# MdA_CPU.net
KiCad netlist of a schematic drawn in Altium Designer
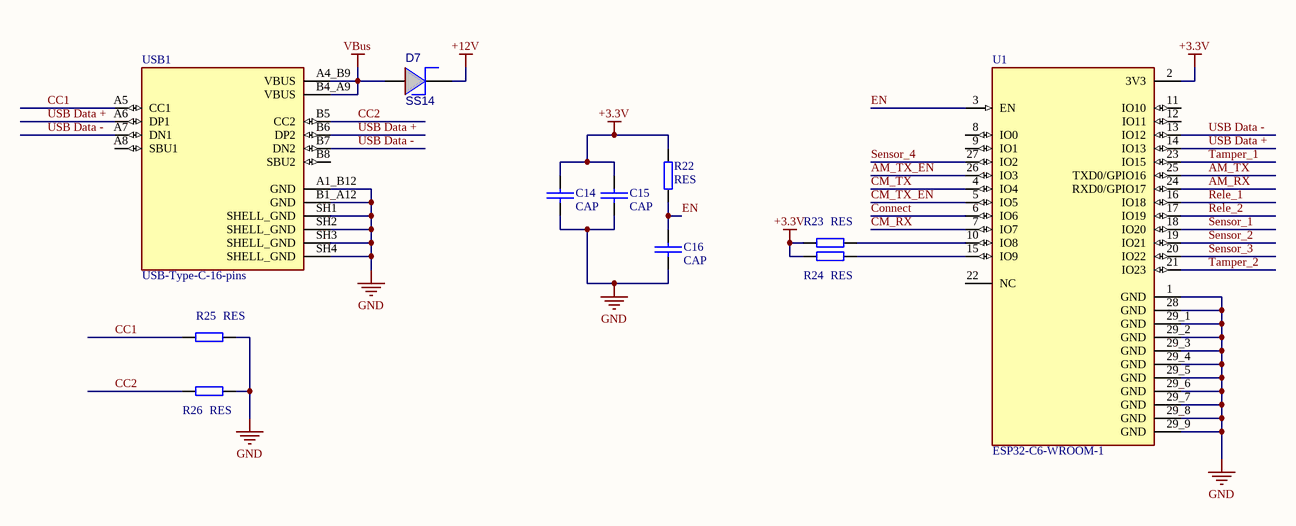
[diagram p0: MdA_CPU.SchDoc]

(export (version "E")
  (design (tool "Eeschema 10.0.6"))
  (components
    (comp (ref "C14") (value "CAP") (footprint "C_0402") (libsource (lib "Modulo de apertura") (part "CAP")))
    (comp (ref "C15") (value "CAP") (footprint "C_0402") (libsource (lib "Modulo de apertura") (part "CAP")))
    (comp (ref "C16") (value "CAP") (footprint "C_0402") (libsource (lib "Modulo de apertura") (part "CAP")))
    (comp (ref "D7")
      (value "SS14")
      (footprint "IDCI_WifiNode:D_SMA")
      (description "Diode Shottky")
      (libsource (lib "WifiNode") (part "DIODO_SH"))
    )
    (comp (ref "R22") (value "RES") (footprint "R_0402") (libsource (lib "Modulo de apertura") (part "RES")))
    (comp (ref "R23") (value "RES") (footprint "R_0402") (libsource (lib "Modulo de apertura") (part "RES")))
    (comp (ref "R24") (value "RES") (footprint "R_0402") (libsource (lib "Modulo de apertura") (part "RES")))
    (comp (ref "R25") (value "RES") (footprint "R_0402") (libsource (lib "Modulo de apertura") (part "RES")))
    (comp (ref "R26") (value "RES") (footprint "R_0402") (libsource (lib "Modulo de apertura") (part "RES")))
    (comp (ref "U1")
      (value "ESP32-C6-WROOM-1")
      (footprint "ESP32-C6-WROOM-1")
      (libsource (lib "Modulo de apertura") (part "ESP32-C6-WROOM-1"))
    )
    (comp (ref "USB1")
      (value "USB-Type-C-16-pins")
      (footprint "GCT_USB4105GFA120")
      (libsource (lib "Modulo de apertura") (part "USB-Type-C-16-pins"))
    )
  )
  (nets
    (net (code "1") (name "+3.3V") (class "Default")
      (node (ref "C14") (pin "1") (pinfunction "1_1") (pintype "passive"))
      (node (ref "C15") (pin "1") (pinfunction "1_1") (pintype "passive"))
      (node (ref "R22") (pin "1") (pinfunction "1_1") (pintype "passive"))
      (node (ref "R23") (pin "2") (pinfunction "2_2") (pintype "passive"))
      (node (ref "R24") (pin "2") (pinfunction "2_2") (pintype "passive"))
      (node (ref "U1") (pin "2") (pinfunction "3V3_2") (pintype "power_in"))
    )
    (net (code "2") (name "+12V") (class "Default")
      (node (ref "D7") (pin "2") (pinfunction "K_2") (pintype "passive"))
    )
    (net (code "3") (name "/AM_RX") (class "Default")
      (node (ref "U1") (pin "24") (pinfunction "RXD0/GPIO17_24") (pintype "bidirectional"))
    )
    (net (code "4") (name "/AM_TX") (class "Default")
      (node (ref "U1") (pin "25") (pinfunction "TXD0/GPIO16_25") (pintype "bidirectional"))
    )
    (net (code "5") (name "/AM_TX_EN") (class "Default")
      (node (ref "U1") (pin "26") (pinfunction "IO3_26") (pintype "bidirectional"))
    )
    (net (code "6") (name "/CC1") (class "Default")
      (node (ref "R25") (pin "2") (pinfunction "2_2") (pintype "passive"))
      (node (ref "USB1") (pin "A5") (pinfunction "CC1_A5") (pintype "bidirectional"))
    )
    (net (code "7") (name "/CC2") (class "Default")
      (node (ref "R26") (pin "2") (pinfunction "2_2") (pintype "passive"))
      (node (ref "USB1") (pin "B5") (pinfunction "CC2_B5") (pintype "bidirectional"))
    )
    (net (code "8") (name "/CM_RX") (class "Default")
      (node (ref "U1") (pin "7") (pinfunction "IO7_7") (pintype "bidirectional"))
    )
    (net (code "9") (name "/CM_TX") (class "Default")
      (node (ref "U1") (pin "4") (pinfunction "IO4_4") (pintype "bidirectional"))
    )
    (net (code "10") (name "/CM_TX_EN") (class "Default")
      (node (ref "U1") (pin "5") (pinfunction "IO5_5") (pintype "bidirectional"))
    )
    (net (code "11") (name "/Connect") (class "Default")
      (node (ref "U1") (pin "6") (pinfunction "IO6_6") (pintype "bidirectional"))
    )
    (net (code "12") (name "/EN") (class "Default")
      (node (ref "C16") (pin "1") (pinfunction "1_1") (pintype "passive"))
      (node (ref "R22") (pin "2") (pinfunction "2_2") (pintype "passive"))
      (node (ref "U1") (pin "3") (pinfunction "EN_3") (pintype "input"))
    )
    (net (code "13") (name "/Rele_1") (class "Default")
      (node (ref "U1") (pin "16") (pinfunction "IO18_16") (pintype "bidirectional"))
    )
    (net (code "14") (name "/Rele_2") (class "Default")
      (node (ref "U1") (pin "17") (pinfunction "IO19_17") (pintype "bidirectional"))
    )
    (net (code "15") (name "/Sensor_1") (class "Default")
      (node (ref "U1") (pin "18") (pinfunction "IO20_18") (pintype "bidirectional"))
    )
    (net (code "16") (name "/Sensor_2") (class "Default")
      (node (ref "U1") (pin "19") (pinfunction "IO21_19") (pintype "bidirectional"))
    )
    (net (code "17") (name "/Sensor_3") (class "Default")
      (node (ref "U1") (pin "20") (pinfunction "IO22_20") (pintype "bidirectional"))
    )
    (net (code "18") (name "/Sensor_4") (class "Default")
      (node (ref "U1") (pin "27") (pinfunction "IO2_27") (pintype "bidirectional"))
    )
    (net (code "19") (name "/Tamper_1") (class "Default")
      (node (ref "U1") (pin "23") (pinfunction "IO15_23") (pintype "bidirectional"))
    )
    (net (code "20") (name "/Tamper_2") (class "Default")
      (node (ref "U1") (pin "21") (pinfunction "IO23_21") (pintype "bidirectional"))
    )
    (net (code "21") (name "/USB Data +") (class "Default")
      (node (ref "U1") (pin "14") (pinfunction "IO13_14") (pintype "bidirectional"))
      (node (ref "USB1") (pin "A6") (pinfunction "DP1_A6") (pintype "bidirectional"))
      (node (ref "USB1") (pin "B6") (pinfunction "DP2_B6") (pintype "bidirectional"))
    )
    (net (code "22") (name "/USB Data -") (class "Default")
      (node (ref "U1") (pin "13") (pinfunction "IO12_13") (pintype "bidirectional"))
      (node (ref "USB1") (pin "A7") (pinfunction "DN1_A7") (pintype "bidirectional"))
      (node (ref "USB1") (pin "B7") (pinfunction "DN2_B7") (pintype "bidirectional"))
    )
    (net (code "23") (name "GND") (class "Default")
      (node (ref "C14") (pin "2") (pinfunction "2_2") (pintype "passive"))
      (node (ref "C15") (pin "2") (pinfunction "2_2") (pintype "passive"))
      (node (ref "C16") (pin "2") (pinfunction "2_2") (pintype "passive"))
      (node (ref "R25") (pin "1") (pinfunction "1_1") (pintype "passive"))
      (node (ref "R26") (pin "1") (pinfunction "1_1") (pintype "passive"))
      (node (ref "U1") (pin "1") (pinfunction "GND_1") (pintype "power_in"))
      (node (ref "U1") (pin "28") (pinfunction "GND_28") (pintype "power_in"))
      (node (ref "U1") (pin "29_1") (pinfunction "GND_29_1") (pintype "power_in"))
      (node (ref "U1") (pin "29_2") (pinfunction "GND_29_2") (pintype "power_in"))
      (node (ref "U1") (pin "29_3") (pinfunction "GND_29_3") (pintype "power_in"))
      (node (ref "U1") (pin "29_4") (pinfunction "GND_29_4") (pintype "power_in"))
      (node (ref "U1") (pin "29_5") (pinfunction "GND_29_5") (pintype "power_in"))
      (node (ref "U1") (pin "29_6") (pinfunction "GND_29_6") (pintype "power_in"))
      (node (ref "U1") (pin "29_7") (pinfunction "GND_29_7") (pintype "power_in"))
      (node (ref "U1") (pin "29_8") (pinfunction "GND_29_8") (pintype "power_in"))
      (node (ref "U1") (pin "29_9") (pinfunction "GND_29_9") (pintype "power_in"))
      (node (ref "USB1") (pin "A1_B12") (pinfunction "GND_A1_B12") (pintype "power_in"))
      (node (ref "USB1") (pin "B1_A12") (pinfunction "GND_B1_A12") (pintype "power_in"))
      (node (ref "USB1") (pin "SH1") (pinfunction "SHELL_GND_SH1") (pintype "power_in"))
      (node (ref "USB1") (pin "SH2") (pinfunction "SHELL_GND_SH2") (pintype "power_in"))
      (node (ref "USB1") (pin "SH3") (pinfunction "SHELL_GND_SH3") (pintype "power_in"))
      (node (ref "USB1") (pin "SH4") (pinfunction "SHELL_GND_SH4") (pintype "power_in"))
    )
    (net (code "24") (name "Net-(U1-IO8)") (class "Default")
      (node (ref "R23") (pin "1") (pinfunction "1_1") (pintype "passive"))
      (node (ref "U1") (pin "10") (pinfunction "IO8_10") (pintype "bidirectional"))
    )
    (net (code "25") (name "Net-(U1-IO9)") (class "Default")
      (node (ref "R24") (pin "1") (pinfunction "1_1") (pintype "passive"))
      (node (ref "U1") (pin "15") (pinfunction "IO9_15") (pintype "bidirectional"))
    )
    (net (code "26") (name "VBus") (class "Default")
      (node (ref "D7") (pin "1") (pinfunction "A_1") (pintype "passive"))
      (node (ref "USB1") (pin "A4_B9") (pinfunction "VBUS_A4_B9") (pintype "power_in"))
      (node (ref "USB1") (pin "B4_A9") (pinfunction "VBUS_B4_A9") (pintype "power_in"))
    )
    (net (code "27") (name "unconnected-(U1-IO0-Pad8)") (class "Default")
      (node (ref "U1") (pin "8") (pinfunction "IO0_8") (pintype "bidirectional"))
    )
    (net (code "28") (name "unconnected-(U1-IO1-Pad9)") (class "Default")
      (node (ref "U1") (pin "9") (pinfunction "IO1_9") (pintype "bidirectional"))
    )
    (net (code "29") (name "unconnected-(U1-IO10-Pad11)") (class "Default")
      (node (ref "U1") (pin "11") (pinfunction "IO10_11") (pintype "bidirectional"))
    )
    (net (code "30") (name "unconnected-(U1-IO11-Pad12)") (class "Default")
      (node (ref "U1") (pin "12") (pinfunction "IO11_12") (pintype "bidirectional"))
    )
    (net (code "31") (name "unconnected-(U1-NC-Pad22)") (class "Default")
      (node (ref "U1") (pin "22") (pinfunction "NC_22") (pintype "passive"))
    )
    (net (code "32") (name "unconnected-(USB1-SBU1-PadA8)") (class "Default")
      (node (ref "USB1") (pin "A8") (pinfunction "SBU1_A8") (pintype "bidirectional"))
    )
    (net (code "33") (name "unconnected-(USB1-SBU2-PadB8)") (class "Default")
      (node (ref "USB1") (pin "B8") (pinfunction "SBU2_B8") (pintype "bidirectional"))
    )
  )
)
